# Antenna.net
KiCad netlist of a schematic drawn in EAGLE
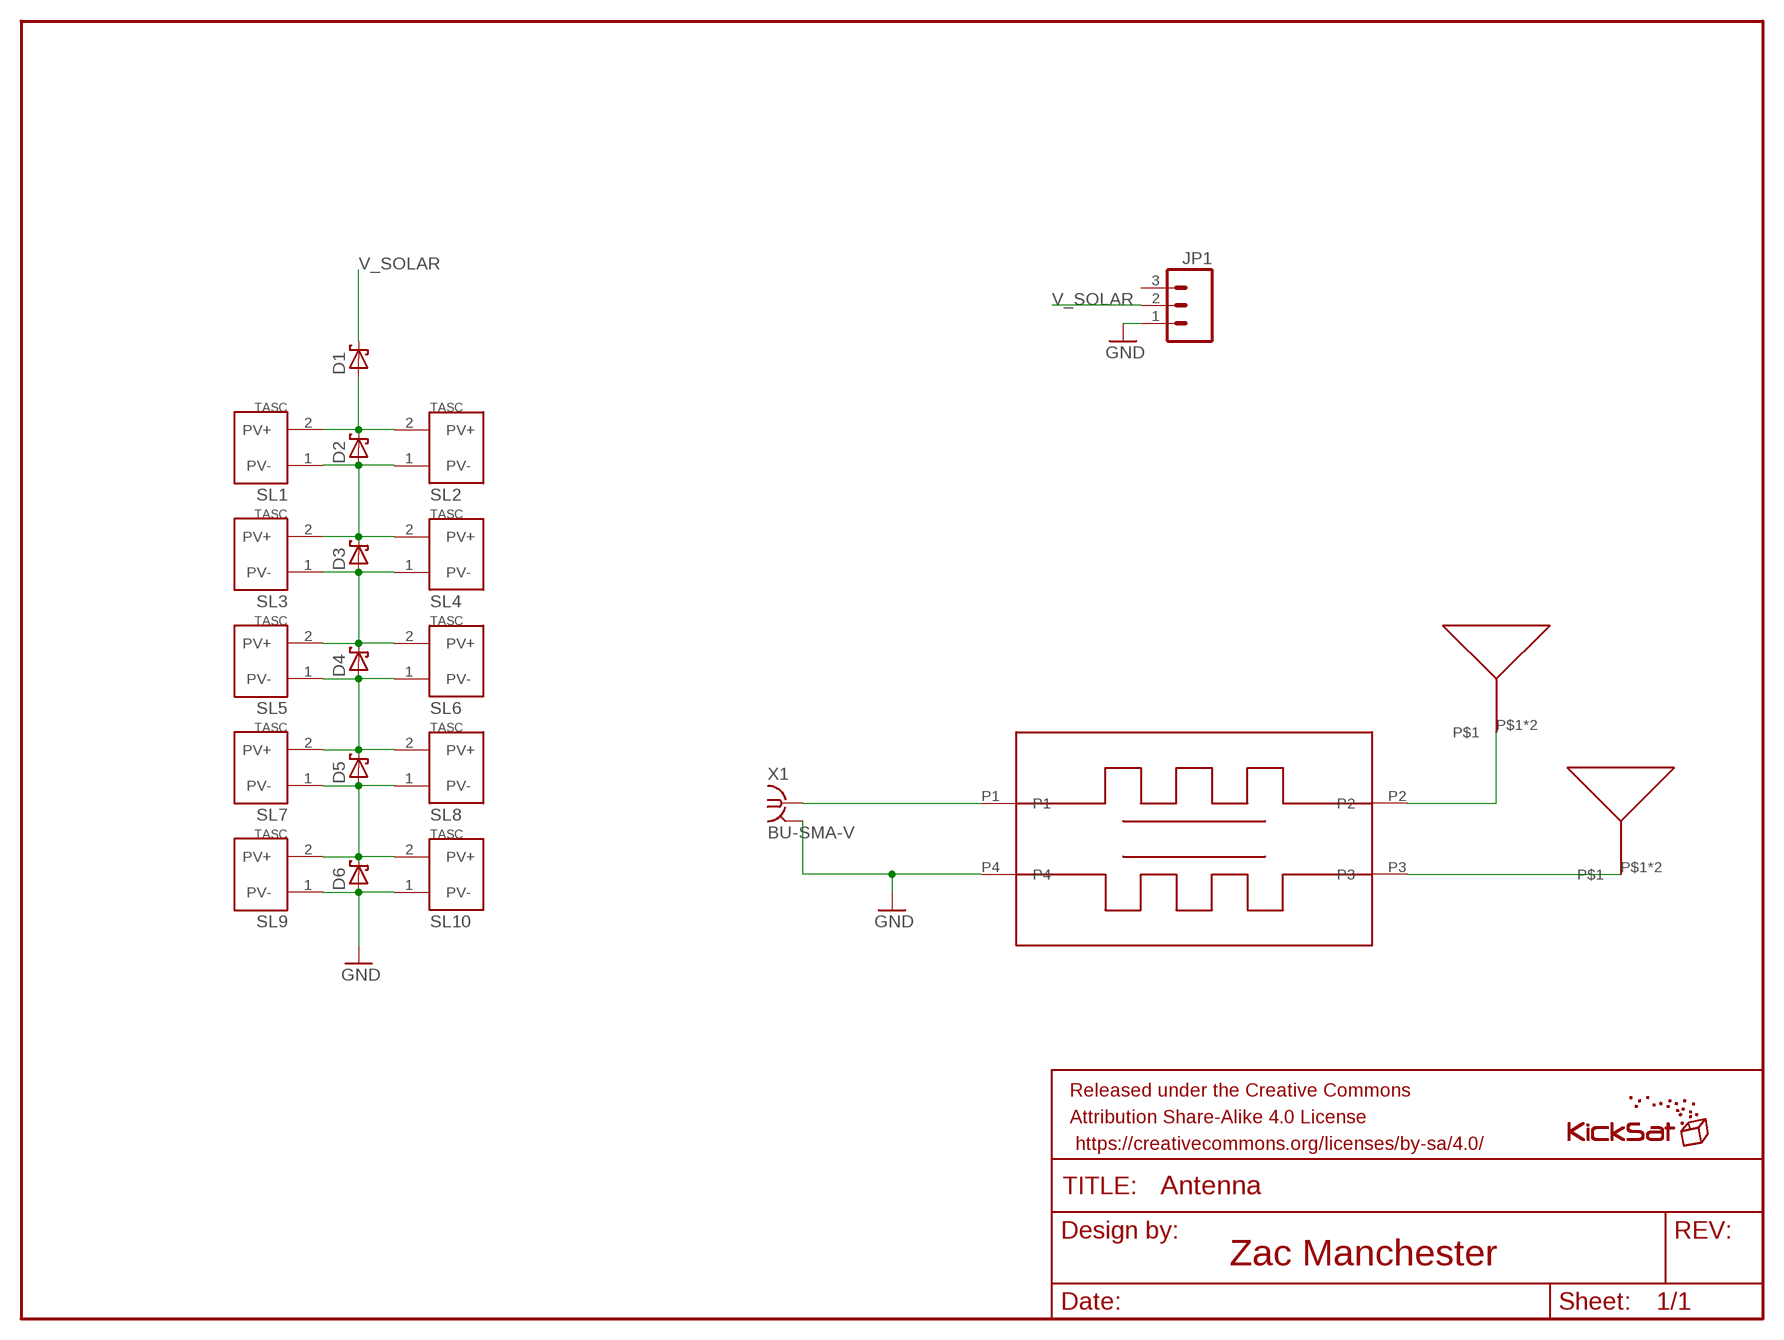
[diagram p0: schematic, sheet 1]

(export (version "E")
  (design (tool "Eeschema 10.0.6"))
  (components
    (comp (ref "B1")
      (value "BALUN")
      (footprint "eagle-import:BALUN")
      (libsource (lib "eagle-import") (part "BALUN"))
    )
    (comp (ref "D1")
      (value "SB_DIODE")
      (footprint "eagle-import:SB_DIODE")
      (libsource (lib "eagle-import") (part "SB_DIODE"))
    )
    (comp (ref "D2")
      (value "SB_DIODE")
      (footprint "eagle-import:SB_DIODE")
      (libsource (lib "eagle-import") (part "SB_DIODE"))
    )
    (comp (ref "D3")
      (value "SB_DIODE")
      (footprint "eagle-import:SB_DIODE")
      (libsource (lib "eagle-import") (part "SB_DIODE"))
    )
    (comp (ref "D4")
      (value "SB_DIODE")
      (footprint "eagle-import:SB_DIODE")
      (libsource (lib "eagle-import") (part "SB_DIODE"))
    )
    (comp (ref "D5")
      (value "SB_DIODE")
      (footprint "eagle-import:SB_DIODE")
      (libsource (lib "eagle-import") (part "SB_DIODE"))
    )
    (comp (ref "D6")
      (value "SB_DIODE")
      (footprint "eagle-import:SB_DIODE")
      (libsource (lib "eagle-import") (part "SB_DIODE"))
    )
    (comp (ref "FRAME1")
      (value "FRAME-LETTER")
      (footprint "eagle-import:CREATIVE_COMMONS")
      (libsource (lib "eagle-import") (part "FRAME-LETTER"))
    )
    (comp (ref "JP1")
      (value "M03POLAR_LOCK")
      (footprint "eagle-import:MOLEX-1X3_LOCK")
      (libsource (lib "eagle-import") (part "M03POLAR_LOCK"))
    )
    (comp (ref "SL1")
      (value "SOLAR_CELL")
      (footprint "eagle-import:SOLAR_CELL")
      (libsource (lib "eagle-import") (part "SOLAR_CELL"))
    )
    (comp (ref "SL2")
      (value "SOLAR_CELL")
      (footprint "eagle-import:SOLAR_CELL")
      (libsource (lib "eagle-import") (part "SOLAR_CELL"))
    )
    (comp (ref "SL3")
      (value "SOLAR_CELL")
      (footprint "eagle-import:SOLAR_CELL")
      (libsource (lib "eagle-import") (part "SOLAR_CELL"))
    )
    (comp (ref "SL4")
      (value "SOLAR_CELL")
      (footprint "eagle-import:SOLAR_CELL")
      (libsource (lib "eagle-import") (part "SOLAR_CELL"))
    )
    (comp (ref "SL5")
      (value "SOLAR_CELL")
      (footprint "eagle-import:SOLAR_CELL")
      (libsource (lib "eagle-import") (part "SOLAR_CELL"))
    )
    (comp (ref "SL6")
      (value "SOLAR_CELL")
      (footprint "eagle-import:SOLAR_CELL")
      (libsource (lib "eagle-import") (part "SOLAR_CELL"))
    )
    (comp (ref "SL7")
      (value "SOLAR_CELL")
      (footprint "eagle-import:SOLAR_CELL")
      (libsource (lib "eagle-import") (part "SOLAR_CELL"))
    )
    (comp (ref "SL8")
      (value "SOLAR_CELL")
      (footprint "eagle-import:SOLAR_CELL")
      (libsource (lib "eagle-import") (part "SOLAR_CELL"))
    )
    (comp (ref "SL9")
      (value "SOLAR_CELL")
      (footprint "eagle-import:SOLAR_CELL")
      (libsource (lib "eagle-import") (part "SOLAR_CELL"))
    )
    (comp (ref "SL10")
      (value "SOLAR_CELL")
      (footprint "eagle-import:SOLAR_CELL")
      (libsource (lib "eagle-import") (part "SOLAR_CELL"))
    )
    (comp (ref "U$1")
      (value "TAPEANTENNA")
      (footprint "eagle-import:TAPEANTENNA")
      (libsource (lib "eagle-import") (part "TAPEANTENNA"))
    )
    (comp (ref "U$2")
      (value "TAPEANTENNA")
      (footprint "eagle-import:TAPEANTENNA")
      (libsource (lib "eagle-import") (part "TAPEANTENNA"))
    )
    (comp (ref "U$3")
      (value "KICKSAT_LOGO")
      (footprint "eagle-import:KICKSAT_LOGO")
      (libsource (lib "eagle-import") (part "KICKSAT_LOGO"))
    )
    (comp (ref "X1")
      (value "BU-SMA-V")
      (footprint "eagle-import:BU-SMA-V")
      (libsource (lib "eagle-import") (part "BU-SMA-V"))
    )
  )
  (nets
    (net (code "1") (name "/V_SOLAR") (class "Default")
      (node (ref "D1") (pin "NEG") (pinfunction "NEG_NEG") (pintype "passive"))
      (node (ref "JP1") (pin "2") (pinfunction "2_2") (pintype "passive"))
    )
    (net (code "2") (name "GND") (class "Default")
      (node (ref "B1") (pin "P4") (pinfunction "P4_P4") (pintype "bidirectional"))
      (node (ref "D6") (pin "POS") (pinfunction "POS_POS") (pintype "passive"))
      (node (ref "JP1") (pin "1") (pinfunction "1_1") (pintype "passive"))
      (node (ref "SL10") (pin "1") (pinfunction "PV-_1") (pintype "bidirectional"))
      (node (ref "SL9") (pin "1") (pinfunction "PV-_1") (pintype "bidirectional"))
      (node (ref "X1") (pin "2") (pinfunction "2_2") (pintype "passive"))
      (node (ref "X1") (pin "3") (pinfunction "2_3") (pintype "passive"))
      (node (ref "X1") (pin "4") (pinfunction "2_4") (pintype "passive"))
      (node (ref "X1") (pin "5") (pinfunction "2_5") (pintype "passive"))
    )
    (net (code "3") (name "Net-(B1-PadP1)") (class "Default")
      (node (ref "B1") (pin "P1") (pinfunction "P1_P1") (pintype "bidirectional"))
      (node (ref "X1") (pin "1") (pinfunction "1_1") (pintype "passive"))
    )
    (net (code "4") (name "Net-(B1-PadP2)") (class "Default")
      (node (ref "B1") (pin "P2") (pinfunction "P2_P2") (pintype "bidirectional"))
      (node (ref "U$1") (pin "P$1") (pinfunction "P$1_P$1") (pintype "bidirectional"))
      (node (ref "U$1") (pin "P$2") (pinfunction "P$1_P$2") (pintype "bidirectional"))
    )
    (net (code "5") (name "Net-(B1-PadP3)") (class "Default")
      (node (ref "B1") (pin "P3") (pinfunction "P3_P3") (pintype "bidirectional"))
      (node (ref "U$2") (pin "P$1") (pinfunction "P$1_P$1") (pintype "bidirectional"))
      (node (ref "U$2") (pin "P$2") (pinfunction "P$1_P$2") (pintype "bidirectional"))
    )
    (net (code "6") (name "Net-(SL1-PV+)") (class "Default")
      (node (ref "D1") (pin "POS") (pinfunction "POS_POS") (pintype "passive"))
      (node (ref "D2") (pin "NEG") (pinfunction "NEG_NEG") (pintype "passive"))
      (node (ref "SL1") (pin "2") (pinfunction "PV+_2") (pintype "bidirectional"))
      (node (ref "SL2") (pin "2") (pinfunction "PV+_2") (pintype "bidirectional"))
    )
    (net (code "7") (name "Net-(SL1-PV-)") (class "Default")
      (node (ref "D2") (pin "POS") (pinfunction "POS_POS") (pintype "passive"))
      (node (ref "D3") (pin "NEG") (pinfunction "NEG_NEG") (pintype "passive"))
      (node (ref "SL1") (pin "1") (pinfunction "PV-_1") (pintype "bidirectional"))
      (node (ref "SL2") (pin "1") (pinfunction "PV-_1") (pintype "bidirectional"))
      (node (ref "SL3") (pin "2") (pinfunction "PV+_2") (pintype "bidirectional"))
      (node (ref "SL4") (pin "2") (pinfunction "PV+_2") (pintype "bidirectional"))
    )
    (net (code "8") (name "Net-(SL3-PV-)") (class "Default")
      (node (ref "D3") (pin "POS") (pinfunction "POS_POS") (pintype "passive"))
      (node (ref "D4") (pin "NEG") (pinfunction "NEG_NEG") (pintype "passive"))
      (node (ref "SL3") (pin "1") (pinfunction "PV-_1") (pintype "bidirectional"))
      (node (ref "SL4") (pin "1") (pinfunction "PV-_1") (pintype "bidirectional"))
      (node (ref "SL5") (pin "2") (pinfunction "PV+_2") (pintype "bidirectional"))
      (node (ref "SL6") (pin "2") (pinfunction "PV+_2") (pintype "bidirectional"))
    )
    (net (code "9") (name "Net-(SL5-PV-)") (class "Default")
      (node (ref "D4") (pin "POS") (pinfunction "POS_POS") (pintype "passive"))
      (node (ref "D5") (pin "NEG") (pinfunction "NEG_NEG") (pintype "passive"))
      (node (ref "SL5") (pin "1") (pinfunction "PV-_1") (pintype "bidirectional"))
      (node (ref "SL6") (pin "1") (pinfunction "PV-_1") (pintype "bidirectional"))
      (node (ref "SL7") (pin "2") (pinfunction "PV+_2") (pintype "bidirectional"))
      (node (ref "SL8") (pin "2") (pinfunction "PV+_2") (pintype "bidirectional"))
    )
    (net (code "10") (name "Net-(SL10-PV+)") (class "Default")
      (node (ref "D5") (pin "POS") (pinfunction "POS_POS") (pintype "passive"))
      (node (ref "D6") (pin "NEG") (pinfunction "NEG_NEG") (pintype "passive"))
      (node (ref "SL10") (pin "2") (pinfunction "PV+_2") (pintype "bidirectional"))
      (node (ref "SL7") (pin "1") (pinfunction "PV-_1") (pintype "bidirectional"))
      (node (ref "SL8") (pin "1") (pinfunction "PV-_1") (pintype "bidirectional"))
      (node (ref "SL9") (pin "2") (pinfunction "PV+_2") (pintype "bidirectional"))
    )
    (net (code "11") (name "unconnected-(JP1-Pad3)") (class "Default")
      (node (ref "JP1") (pin "3") (pinfunction "3_3") (pintype "passive"))
    )
  )
)
